# pilar_3.net
KiCad netlist of a schematic drawn in Altium Designer
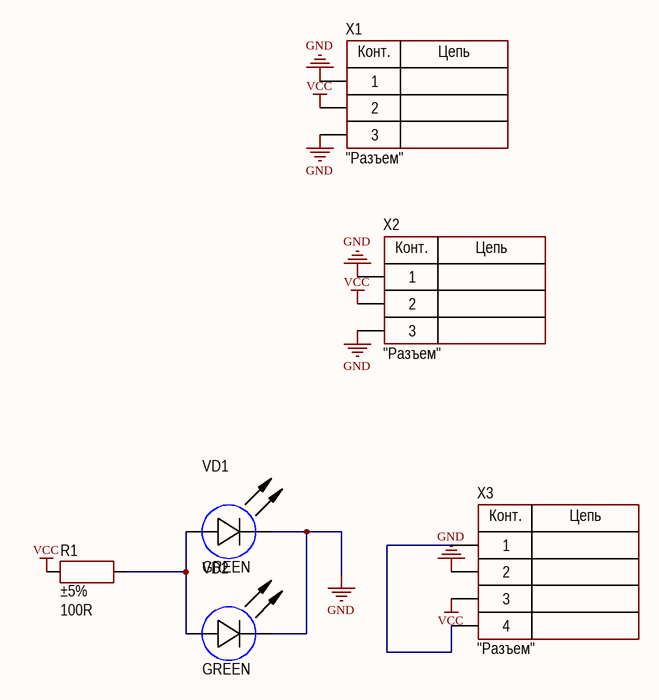
[diagram p0: pilar_3.SchDoc]

(export (version "E")
  (design (tool "Eeschema 10.0.6"))
  (components
    (comp (ref "R1")
      (value "100R")
      (footprint "RES: 0603")
      (fields
        (field (name "MANUFACTURER") "Yageo")
        (field (name "PARTNUMBER") "RC0603JR-07100RL")
        (field (name "VALUEMANUFACTURERPARTNUMBER") "Resistor film, 100R, ±5%, 0603, 0.1W, -55...+125°C")
        (field (name "TOLERANCE") "±5%")
      )
      (libsource (lib "Resistor") (part "Resistor_0603"))
    )
    (comp (ref "VD1")
      (value "~")
      (footprint "LED: 0805R")
      (fields
        (field (name "VALUEMANUFACTURERPARTNUMBER") "LED, *, *, *, -55...+150°C")
        (field (name "COLOR") "GREEN")
      )
      (libsource (lib "Diode") (part "LED_single"))
    )
    (comp (ref "VD2")
      (value "~")
      (footprint "LED: 0805R")
      (fields
        (field (name "VALUEMANUFACTURERPARTNUMBER") "LED, *, *, *, -55...+150°C")
        (field (name "COLOR") "GREEN")
      )
      (libsource (lib "Diode") (part "LED_single"))
    )
    (comp (ref "X1")
      (value "~")
      (footprint "CON: PLS-3")
      (fields
        (field (name "MANUFACTURER") "Connfly")
        (field (name "VALUEMANUFACTURERPARTNUMBER") "Connector, 3pin, 2.54mm, 500VAC, 3A")
        (field (name "PARTNUMBER") "PLS-3")
        (field (name "COMMENTTEXT") "\"Разъем\"")
      )
      (libsource (lib "Connector") (part "PLS-3"))
    )
    (comp (ref "X2")
      (value "~")
      (footprint "CON: PLS-3")
      (fields
        (field (name "MANUFACTURER") "Connfly")
        (field (name "VALUEMANUFACTURERPARTNUMBER") "Connector, 3pin, 2.54mm, 500VAC, 3A")
        (field (name "PARTNUMBER") "PLS-3")
        (field (name "COMMENTTEXT") "\"Разъем\"")
      )
      (libsource (lib "Connector") (part "PLS-3"))
    )
    (comp (ref "X3")
      (value "~")
      (footprint "4PLS RIGHT ANGLE 2")
      (fields
        (field (name "MANUFACTURER") "Connfly")
        (field (name "VALUEMANUFACTURERPARTNUMBER") "Connector, 4pin, 2.54mm, 500VAC, 3A")
        (field (name "PARTNUMBER") "PLS-4")
        (field (name "COMMENTTEXT") "\"Разъем\"")
      )
      (libsource (lib "Connector") (part "PLS-4"))
    )
  )
  (nets
    (net (code "1") (name "GND") (class "Default")
      (node (ref "VD1") (pin "2") (pinfunction "C_2") (pintype "passive"))
      (node (ref "VD2") (pin "2") (pinfunction "C_2") (pintype "passive"))
      (node (ref "X1") (pin "1") (pinfunction "1_1") (pintype "passive"))
      (node (ref "X1") (pin "3") (pinfunction "3_3") (pintype "power_in"))
      (node (ref "X2") (pin "1") (pinfunction "1_1") (pintype "passive"))
      (node (ref "X2") (pin "3") (pinfunction "3_3") (pintype "power_in"))
      (node (ref "X3") (pin "2") (pinfunction "2_2") (pintype "passive"))
    )
    (net (code "2") (name "Net-(VD1-A)") (class "Default")
      (node (ref "R1") (pin "2") (pinfunction "2_2") (pintype "passive"))
      (node (ref "VD1") (pin "1") (pinfunction "A_1") (pintype "passive"))
      (node (ref "VD2") (pin "1") (pinfunction "A_1") (pintype "passive"))
    )
    (net (code "3") (name "Net-(X3-Pad1)") (class "Default")
      (node (ref "X3") (pin "1") (pinfunction "1_1") (pintype "passive"))
      (node (ref "X3") (pin "4") (pinfunction "4_4") (pintype "power_in"))
    )
    (net (code "4") (name "VCC") (class "Default")
      (node (ref "R1") (pin "1") (pinfunction "1_1") (pintype "passive"))
      (node (ref "X1") (pin "2") (pinfunction "2_2") (pintype "passive"))
      (node (ref "X2") (pin "2") (pinfunction "2_2") (pintype "passive"))
      (node (ref "X3") (pin "3") (pinfunction "3_3") (pintype "power_in"))
    )
  )
)
